# OLED_1_3INCH_I2C.net
KiCad netlist of a schematic drawn in EAGLE
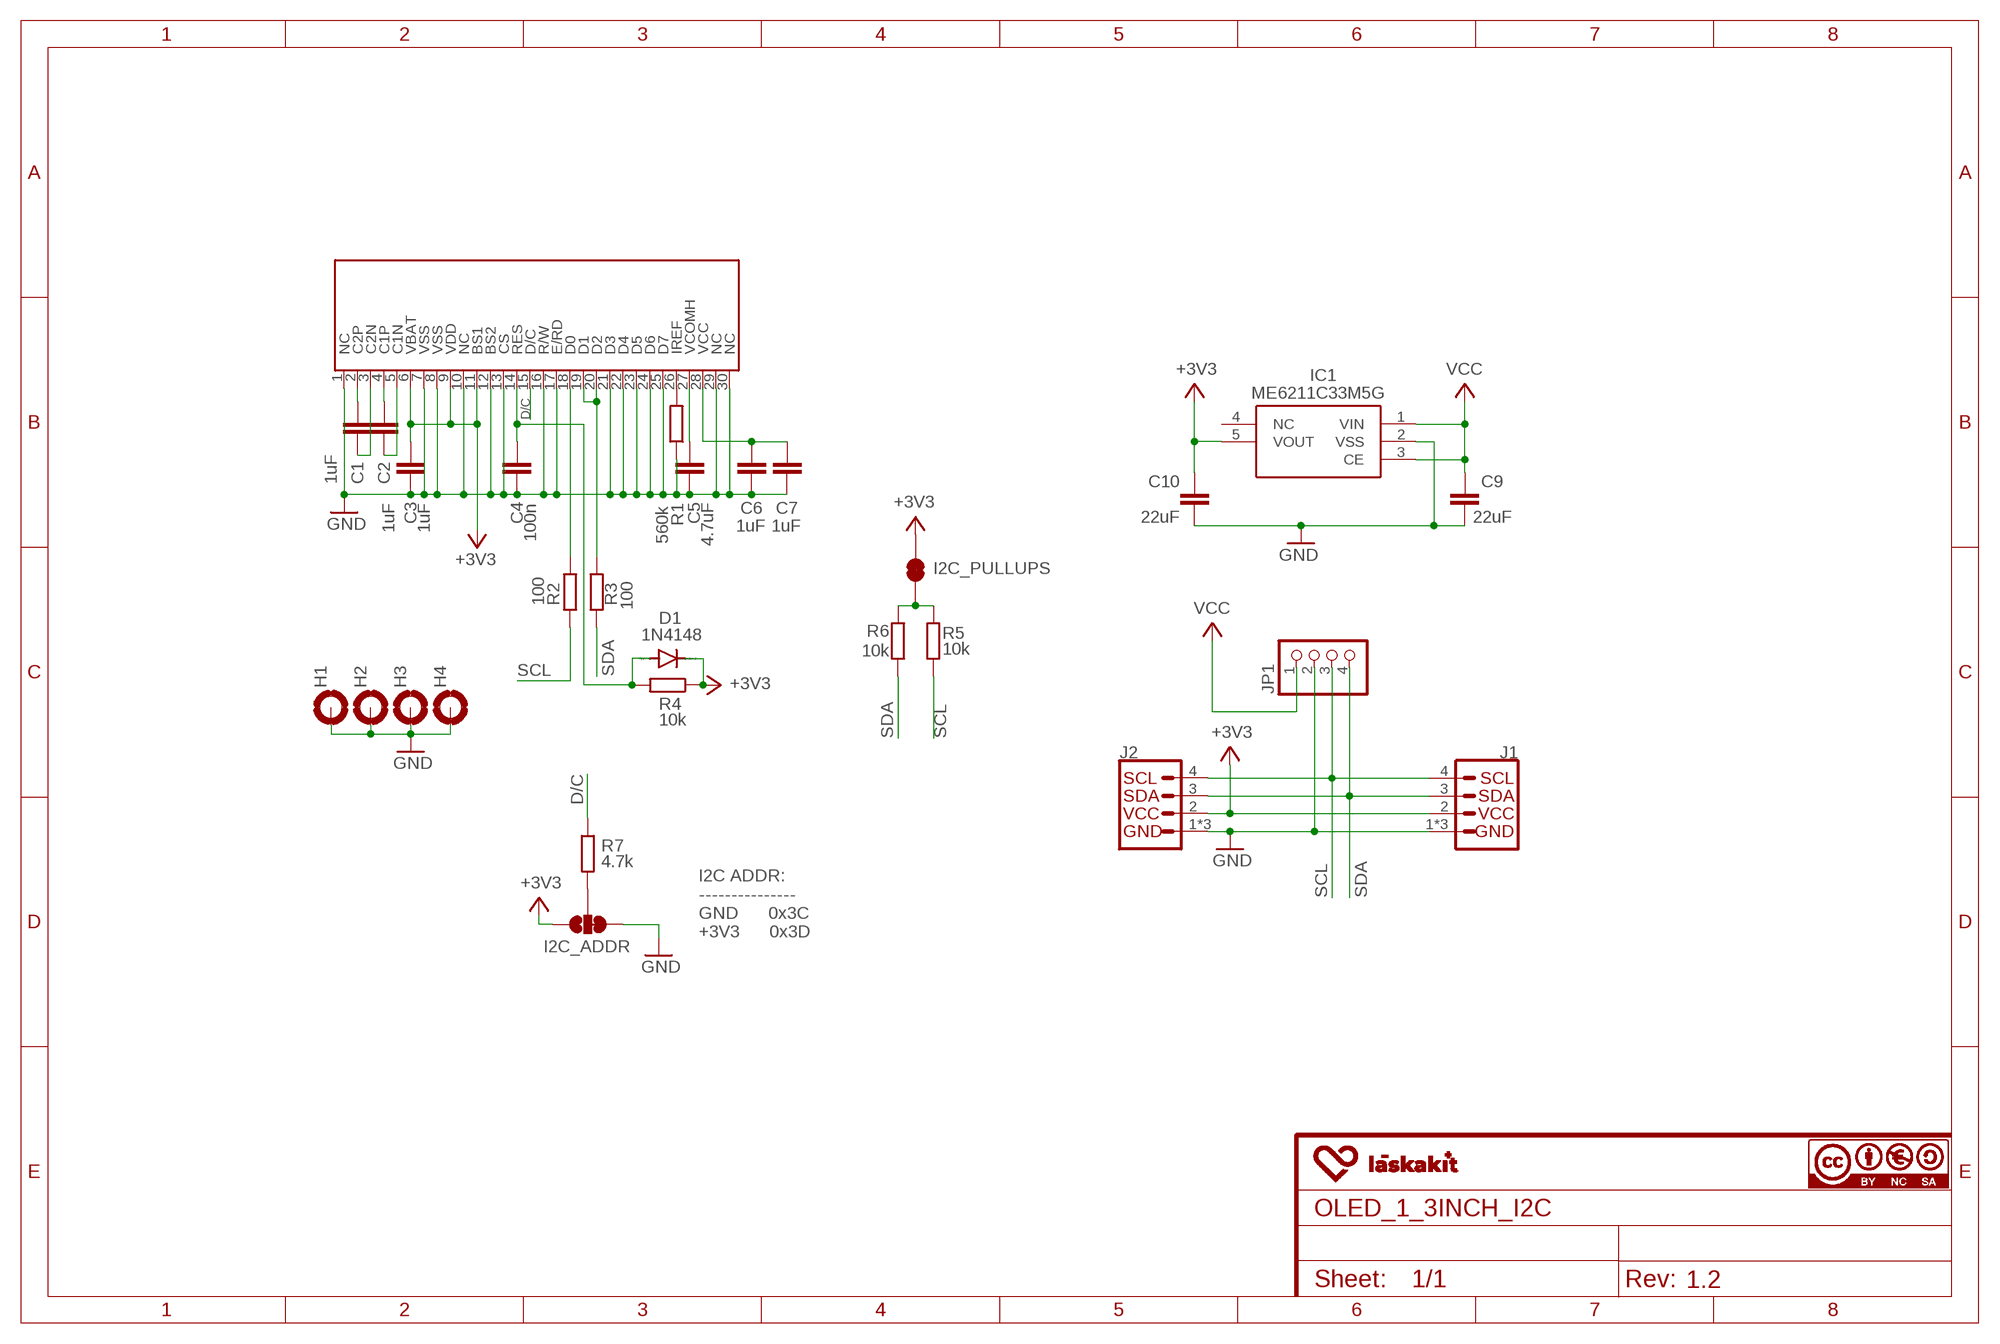
[diagram p0: schematic, sheet 1]

(export (version "E")
  (design (tool "Eeschema 10.0.6"))
  (components
    (comp (ref "C1")
      (value "1uF")
      (footprint "eagle-import:C0603")
      (libsource (lib "eagle-import") (part "C-EUC0603"))
    )
    (comp (ref "C2")
      (value "1uF")
      (footprint "eagle-import:C0603")
      (libsource (lib "eagle-import") (part "C-EUC0603"))
    )
    (comp (ref "C3")
      (value "1uF")
      (footprint "eagle-import:C0603")
      (libsource (lib "eagle-import") (part "C-EUC0603"))
    )
    (comp (ref "C4")
      (value "100n")
      (footprint "eagle-import:C0603")
      (libsource (lib "eagle-import") (part "C-EUC0603"))
    )
    (comp (ref "C5")
      (value "4.7uF")
      (footprint "eagle-import:C0603")
      (libsource (lib "eagle-import") (part "C-EUC0603"))
    )
    (comp (ref "C6")
      (value "1uF")
      (footprint "eagle-import:C0603")
      (libsource (lib "eagle-import") (part "C-EUC0603"))
    )
    (comp (ref "C7")
      (value "1uF")
      (footprint "eagle-import:C0603")
      (libsource (lib "eagle-import") (part "C-EUC0603"))
    )
    (comp (ref "C9")
      (value "22uF")
      (footprint "eagle-import:C0603")
      (libsource (lib "eagle-import") (part "C-EUC0603"))
    )
    (comp (ref "C10")
      (value "22uF")
      (footprint "eagle-import:C0603")
      (libsource (lib "eagle-import") (part "C-EUC0603"))
    )
    (comp (ref "D1")
      (value "1N4148")
      (footprint "eagle-import:SOD323-R")
      (libsource (lib "eagle-import") (part "DIODE-SOD323-R"))
    )
    (comp (ref "DISPLAY1")
      (value "OLED_1_3INCH")
      (footprint "eagle-import:GME12864_1_3INCH")
      (libsource (lib "eagle-import") (part "OLED_1_3INCH"))
    )
    (comp (ref "H1")
      (value "MOUNT-PAD-ROUND2.5")
      (footprint "eagle-import:2,5-PAD")
      (libsource (lib "eagle-import") (part "MOUNT-PAD-ROUND2.5"))
    )
    (comp (ref "H2")
      (value "MOUNT-PAD-ROUND2.5")
      (footprint "eagle-import:2,5-PAD")
      (libsource (lib "eagle-import") (part "MOUNT-PAD-ROUND2.5"))
    )
    (comp (ref "H3")
      (value "MOUNT-PAD-ROUND2.5")
      (footprint "eagle-import:2,5-PAD")
      (libsource (lib "eagle-import") (part "MOUNT-PAD-ROUND2.5"))
    )
    (comp (ref "H4")
      (value "MOUNT-PAD-ROUND2.5")
      (footprint "eagle-import:2,5-PAD")
      (libsource (lib "eagle-import") (part "MOUNT-PAD-ROUND2.5"))
    )
    (comp (ref "I2C_ADDR")
      (value "JUMPER-SMT_3_1-NC_TRACE_NO-SILK")
      (footprint "eagle-import:SMT-JUMPER_3_1-NC_TRACE_NO-SILK")
      (libsource (lib "eagle-import") (part "JUMPER-SMT_3_1-NC_TRACE_NO-SILK"))
    )
    (comp (ref "I2C_PULLUPS")
      (value "JUMPER-SMT_2_NC_TRACE_SILK")
      (footprint "eagle-import:SMT-JUMPER_2_NC_TRACE_SILK")
      (libsource (lib "eagle-import") (part "JUMPER-SMT_2_NC_TRACE_SILK"))
    )
    (comp (ref "IC1")
      (value "ME6211C33M5G")
      (footprint "eagle-import:SOT23-5")
      (libsource (lib "eagle-import") (part "LDO_ME6211C33M5G"))
    )
    (comp (ref "J1")
      (value "USUP_CONNECTOR_HOR")
      (footprint "eagle-import:1X04_1MM_RA")
      (fields (field (name "LCSC_PART") "C145956"))
      (libsource (lib "eagle-import") (part "USUP_CONNECTOR_HOR"))
    )
    (comp (ref "J2")
      (value "USUP_CONNECTOR_HOR")
      (footprint "eagle-import:1X04_1MM_RA")
      (fields (field (name "LCSC_PART") "C145956"))
      (libsource (lib "eagle-import") (part "USUP_CONNECTOR_HOR"))
    )
    (comp (ref "JP1")
      (value "PINHD-1X4")
      (footprint "eagle-import:1X04")
      (libsource (lib "eagle-import") (part "PINHD-1X4"))
    )
    (comp (ref "R1")
      (value "560k")
      (footprint "eagle-import:R0603")
      (libsource (lib "eagle-import") (part "R-EU_R0603"))
    )
    (comp (ref "R2")
      (value "100")
      (footprint "eagle-import:R0603")
      (libsource (lib "eagle-import") (part "R-EU_R0603"))
    )
    (comp (ref "R3")
      (value "100")
      (footprint "eagle-import:R0603")
      (libsource (lib "eagle-import") (part "R-EU_R0603"))
    )
    (comp (ref "R4")
      (value "10k")
      (footprint "eagle-import:R0603")
      (libsource (lib "eagle-import") (part "R-EU_R0603"))
    )
    (comp (ref "R5")
      (value "10k")
      (footprint "eagle-import:R0603")
      (libsource (lib "eagle-import") (part "R-EU_R0603"))
    )
    (comp (ref "R6")
      (value "10k")
      (footprint "eagle-import:R0603")
      (libsource (lib "eagle-import") (part "R-EU_R0603"))
    )
    (comp (ref "R7")
      (value "4.7k")
      (footprint "eagle-import:R0603")
      (libsource (lib "eagle-import") (part "R-EU_R0603"))
    )
  )
  (nets
    (net (code "1") (name "+3V3") (class "Default")
      (node (ref "C10") (pin "1") (pinfunction "1_1") (pintype "passive"))
      (node (ref "C3") (pin "1") (pinfunction "1_1") (pintype "passive"))
      (node (ref "D1") (pin "C") (pinfunction "C_C") (pintype "passive"))
      (node (ref "DISPLAY1") (pin "11") (pinfunction "BS1_11") (pintype "bidirectional"))
      (node (ref "DISPLAY1") (pin "6") (pinfunction "VBAT_6") (pintype "bidirectional"))
      (node (ref "DISPLAY1") (pin "9") (pinfunction "VDD_9") (pintype "bidirectional"))
      (node (ref "I2C_ADDR") (pin "1") (pinfunction "1_1") (pintype "passive"))
      (node (ref "I2C_PULLUPS") (pin "2") (pinfunction "2_2") (pintype "passive"))
      (node (ref "IC1") (pin "5") (pinfunction "VOUT_5") (pintype "bidirectional"))
      (node (ref "J1") (pin "2") (pinfunction "VCC_2") (pintype "power_in"))
      (node (ref "J2") (pin "2") (pinfunction "VCC_2") (pintype "power_in"))
      (node (ref "R4") (pin "1") (pinfunction "1_1") (pintype "passive"))
    )
    (net (code "2") (name "/D{slash}C") (class "Default")
      (node (ref "DISPLAY1") (pin "15") (pinfunction "D/C_15") (pintype "bidirectional"))
      (node (ref "R7") (pin "1") (pinfunction "1_1") (pintype "passive"))
    )
    (net (code "3") (name "/SCL") (class "Default")
      (node (ref "J1") (pin "4") (pinfunction "SCL_4") (pintype "passive"))
      (node (ref "J2") (pin "4") (pinfunction "SCL_4") (pintype "passive"))
      (node (ref "JP1") (pin "3") (pinfunction "3_3") (pintype "passive"))
      (node (ref "R2") (pin "1") (pinfunction "1_1") (pintype "passive"))
      (node (ref "R5") (pin "2") (pinfunction "2_2") (pintype "passive"))
    )
    (net (code "4") (name "/SDA") (class "Default")
      (node (ref "J1") (pin "3") (pinfunction "SDA_3") (pintype "passive"))
      (node (ref "J2") (pin "3") (pinfunction "SDA_3") (pintype "passive"))
      (node (ref "JP1") (pin "4") (pinfunction "4_4") (pintype "passive"))
      (node (ref "R3") (pin "1") (pinfunction "1_1") (pintype "passive"))
      (node (ref "R6") (pin "2") (pinfunction "2_2") (pintype "passive"))
    )
    (net (code "5") (name "GND") (class "Default")
      (node (ref "C10") (pin "2") (pinfunction "2_2") (pintype "passive"))
      (node (ref "C3") (pin "2") (pinfunction "2_2") (pintype "passive"))
      (node (ref "C4") (pin "2") (pinfunction "2_2") (pintype "passive"))
      (node (ref "C5") (pin "2") (pinfunction "2_2") (pintype "passive"))
      (node (ref "C6") (pin "2") (pinfunction "2_2") (pintype "passive"))
      (node (ref "C7") (pin "2") (pinfunction "2_2") (pintype "passive"))
      (node (ref "C9") (pin "2") (pinfunction "2_2") (pintype "passive"))
      (node (ref "DISPLAY1") (pin "1") (pinfunction "NC_1") (pintype "bidirectional"))
      (node (ref "DISPLAY1") (pin "10") (pinfunction "NC_10") (pintype "bidirectional"))
      (node (ref "DISPLAY1") (pin "12") (pinfunction "BS2_12") (pintype "bidirectional"))
      (node (ref "DISPLAY1") (pin "13") (pinfunction "CS_13") (pintype "bidirectional"))
      (node (ref "DISPLAY1") (pin "16") (pinfunction "R/W_16") (pintype "bidirectional"))
      (node (ref "DISPLAY1") (pin "17") (pinfunction "E/RD_17") (pintype "bidirectional"))
      (node (ref "DISPLAY1") (pin "21") (pinfunction "D3_21") (pintype "bidirectional"))
      (node (ref "DISPLAY1") (pin "22") (pinfunction "D4_22") (pintype "bidirectional"))
      (node (ref "DISPLAY1") (pin "23") (pinfunction "D5_23") (pintype "bidirectional"))
      (node (ref "DISPLAY1") (pin "24") (pinfunction "D6_24") (pintype "bidirectional"))
      (node (ref "DISPLAY1") (pin "25") (pinfunction "D7_25") (pintype "bidirectional"))
      (node (ref "DISPLAY1") (pin "29") (pinfunction "NC_29") (pintype "bidirectional"))
      (node (ref "DISPLAY1") (pin "30") (pinfunction "NC_30") (pintype "bidirectional"))
      (node (ref "DISPLAY1") (pin "7") (pinfunction "VSS_7") (pintype "bidirectional"))
      (node (ref "DISPLAY1") (pin "8") (pinfunction "VSS_8") (pintype "bidirectional"))
      (node (ref "H1") (pin "1") (pinfunction "MOUNT_1") (pintype "passive"))
      (node (ref "H2") (pin "1") (pinfunction "MOUNT_1") (pintype "passive"))
      (node (ref "H3") (pin "1") (pinfunction "MOUNT_1") (pintype "passive"))
      (node (ref "H4") (pin "1") (pinfunction "MOUNT_1") (pintype "passive"))
      (node (ref "I2C_ADDR") (pin "3") (pinfunction "3_3") (pintype "passive"))
      (node (ref "IC1") (pin "2") (pinfunction "VSS_2") (pintype "bidirectional"))
      (node (ref "J1") (pin "1") (pinfunction "GND_1") (pintype "power_in"))
      (node (ref "J1") (pin "NC1") (pinfunction "GND_NC1") (pintype "power_in"))
      (node (ref "J1") (pin "NC2") (pinfunction "GND_NC2") (pintype "power_in"))
      (node (ref "J2") (pin "1") (pinfunction "GND_1") (pintype "power_in"))
      (node (ref "J2") (pin "NC1") (pinfunction "GND_NC1") (pintype "power_in"))
      (node (ref "J2") (pin "NC2") (pinfunction "GND_NC2") (pintype "power_in"))
      (node (ref "JP1") (pin "2") (pinfunction "2_2") (pintype "passive"))
      (node (ref "R1") (pin "1") (pinfunction "1_1") (pintype "passive"))
    )
    (net (code "6") (name "Net-(DISPLAY1-C1N)") (class "Default")
      (node (ref "C2") (pin "2") (pinfunction "2_2") (pintype "passive"))
      (node (ref "DISPLAY1") (pin "5") (pinfunction "C1N_5") (pintype "bidirectional"))
    )
    (net (code "7") (name "Net-(DISPLAY1-C1P)") (class "Default")
      (node (ref "C2") (pin "1") (pinfunction "1_1") (pintype "passive"))
      (node (ref "DISPLAY1") (pin "4") (pinfunction "C1P_4") (pintype "bidirectional"))
    )
    (net (code "8") (name "Net-(DISPLAY1-C2N)") (class "Default")
      (node (ref "C1") (pin "2") (pinfunction "2_2") (pintype "passive"))
      (node (ref "DISPLAY1") (pin "3") (pinfunction "C2N_3") (pintype "bidirectional"))
    )
    (net (code "9") (name "Net-(DISPLAY1-C2P)") (class "Default")
      (node (ref "C1") (pin "1") (pinfunction "1_1") (pintype "passive"))
      (node (ref "DISPLAY1") (pin "2") (pinfunction "C2P_2") (pintype "bidirectional"))
    )
    (net (code "10") (name "Net-(DISPLAY1-D0)") (class "Default")
      (node (ref "DISPLAY1") (pin "18") (pinfunction "D0_18") (pintype "bidirectional"))
      (node (ref "R2") (pin "2") (pinfunction "2_2") (pintype "passive"))
    )
    (net (code "11") (name "Net-(DISPLAY1-D1)") (class "Default")
      (node (ref "DISPLAY1") (pin "19") (pinfunction "D1_19") (pintype "bidirectional"))
      (node (ref "DISPLAY1") (pin "20") (pinfunction "D2_20") (pintype "bidirectional"))
      (node (ref "R3") (pin "2") (pinfunction "2_2") (pintype "passive"))
    )
    (net (code "12") (name "Net-(DISPLAY1-IREF)") (class "Default")
      (node (ref "DISPLAY1") (pin "26") (pinfunction "IREF_26") (pintype "bidirectional"))
      (node (ref "R1") (pin "2") (pinfunction "2_2") (pintype "passive"))
    )
    (net (code "13") (name "Net-(DISPLAY1-RES)") (class "Default")
      (node (ref "C4") (pin "1") (pinfunction "1_1") (pintype "passive"))
      (node (ref "D1") (pin "A") (pinfunction "A_A") (pintype "passive"))
      (node (ref "DISPLAY1") (pin "14") (pinfunction "RES_14") (pintype "bidirectional"))
      (node (ref "R4") (pin "2") (pinfunction "2_2") (pintype "passive"))
    )
    (net (code "14") (name "Net-(DISPLAY1-VCC)") (class "Default")
      (node (ref "C6") (pin "1") (pinfunction "1_1") (pintype "passive"))
      (node (ref "C7") (pin "1") (pinfunction "1_1") (pintype "passive"))
      (node (ref "DISPLAY1") (pin "28") (pinfunction "VCC_28") (pintype "bidirectional"))
    )
    (net (code "15") (name "Net-(DISPLAY1-VCOMH)") (class "Default")
      (node (ref "C5") (pin "1") (pinfunction "1_1") (pintype "passive"))
      (node (ref "DISPLAY1") (pin "27") (pinfunction "VCOMH_27") (pintype "bidirectional"))
    )
    (net (code "16") (name "Net-(I2C_ADDR-Pad2)") (class "Default")
      (node (ref "I2C_ADDR") (pin "2") (pinfunction "2_2") (pintype "passive"))
      (node (ref "R7") (pin "2") (pinfunction "2_2") (pintype "passive"))
    )
    (net (code "17") (name "Net-(I2C_PULLUPS-Pad1)") (class "Default")
      (node (ref "I2C_PULLUPS") (pin "1") (pinfunction "1_1") (pintype "passive"))
      (node (ref "R5") (pin "1") (pinfunction "1_1") (pintype "passive"))
      (node (ref "R6") (pin "1") (pinfunction "1_1") (pintype "passive"))
    )
    (net (code "18") (name "VCC") (class "Default")
      (node (ref "C9") (pin "1") (pinfunction "1_1") (pintype "passive"))
      (node (ref "IC1") (pin "1") (pinfunction "VIN_1") (pintype "bidirectional"))
      (node (ref "IC1") (pin "3") (pinfunction "CE_3") (pintype "bidirectional"))
      (node (ref "JP1") (pin "1") (pinfunction "1_1") (pintype "passive"))
    )
    (net (code "19") (name "unconnected-(IC1-NC-Pad4)") (class "Default")
      (node (ref "IC1") (pin "4") (pinfunction "NC_4") (pintype "no_connect"))
    )
  )
)
